# Mainsnode_v2_openmote.net
KiCad netlist of a schematic drawn in EAGLE
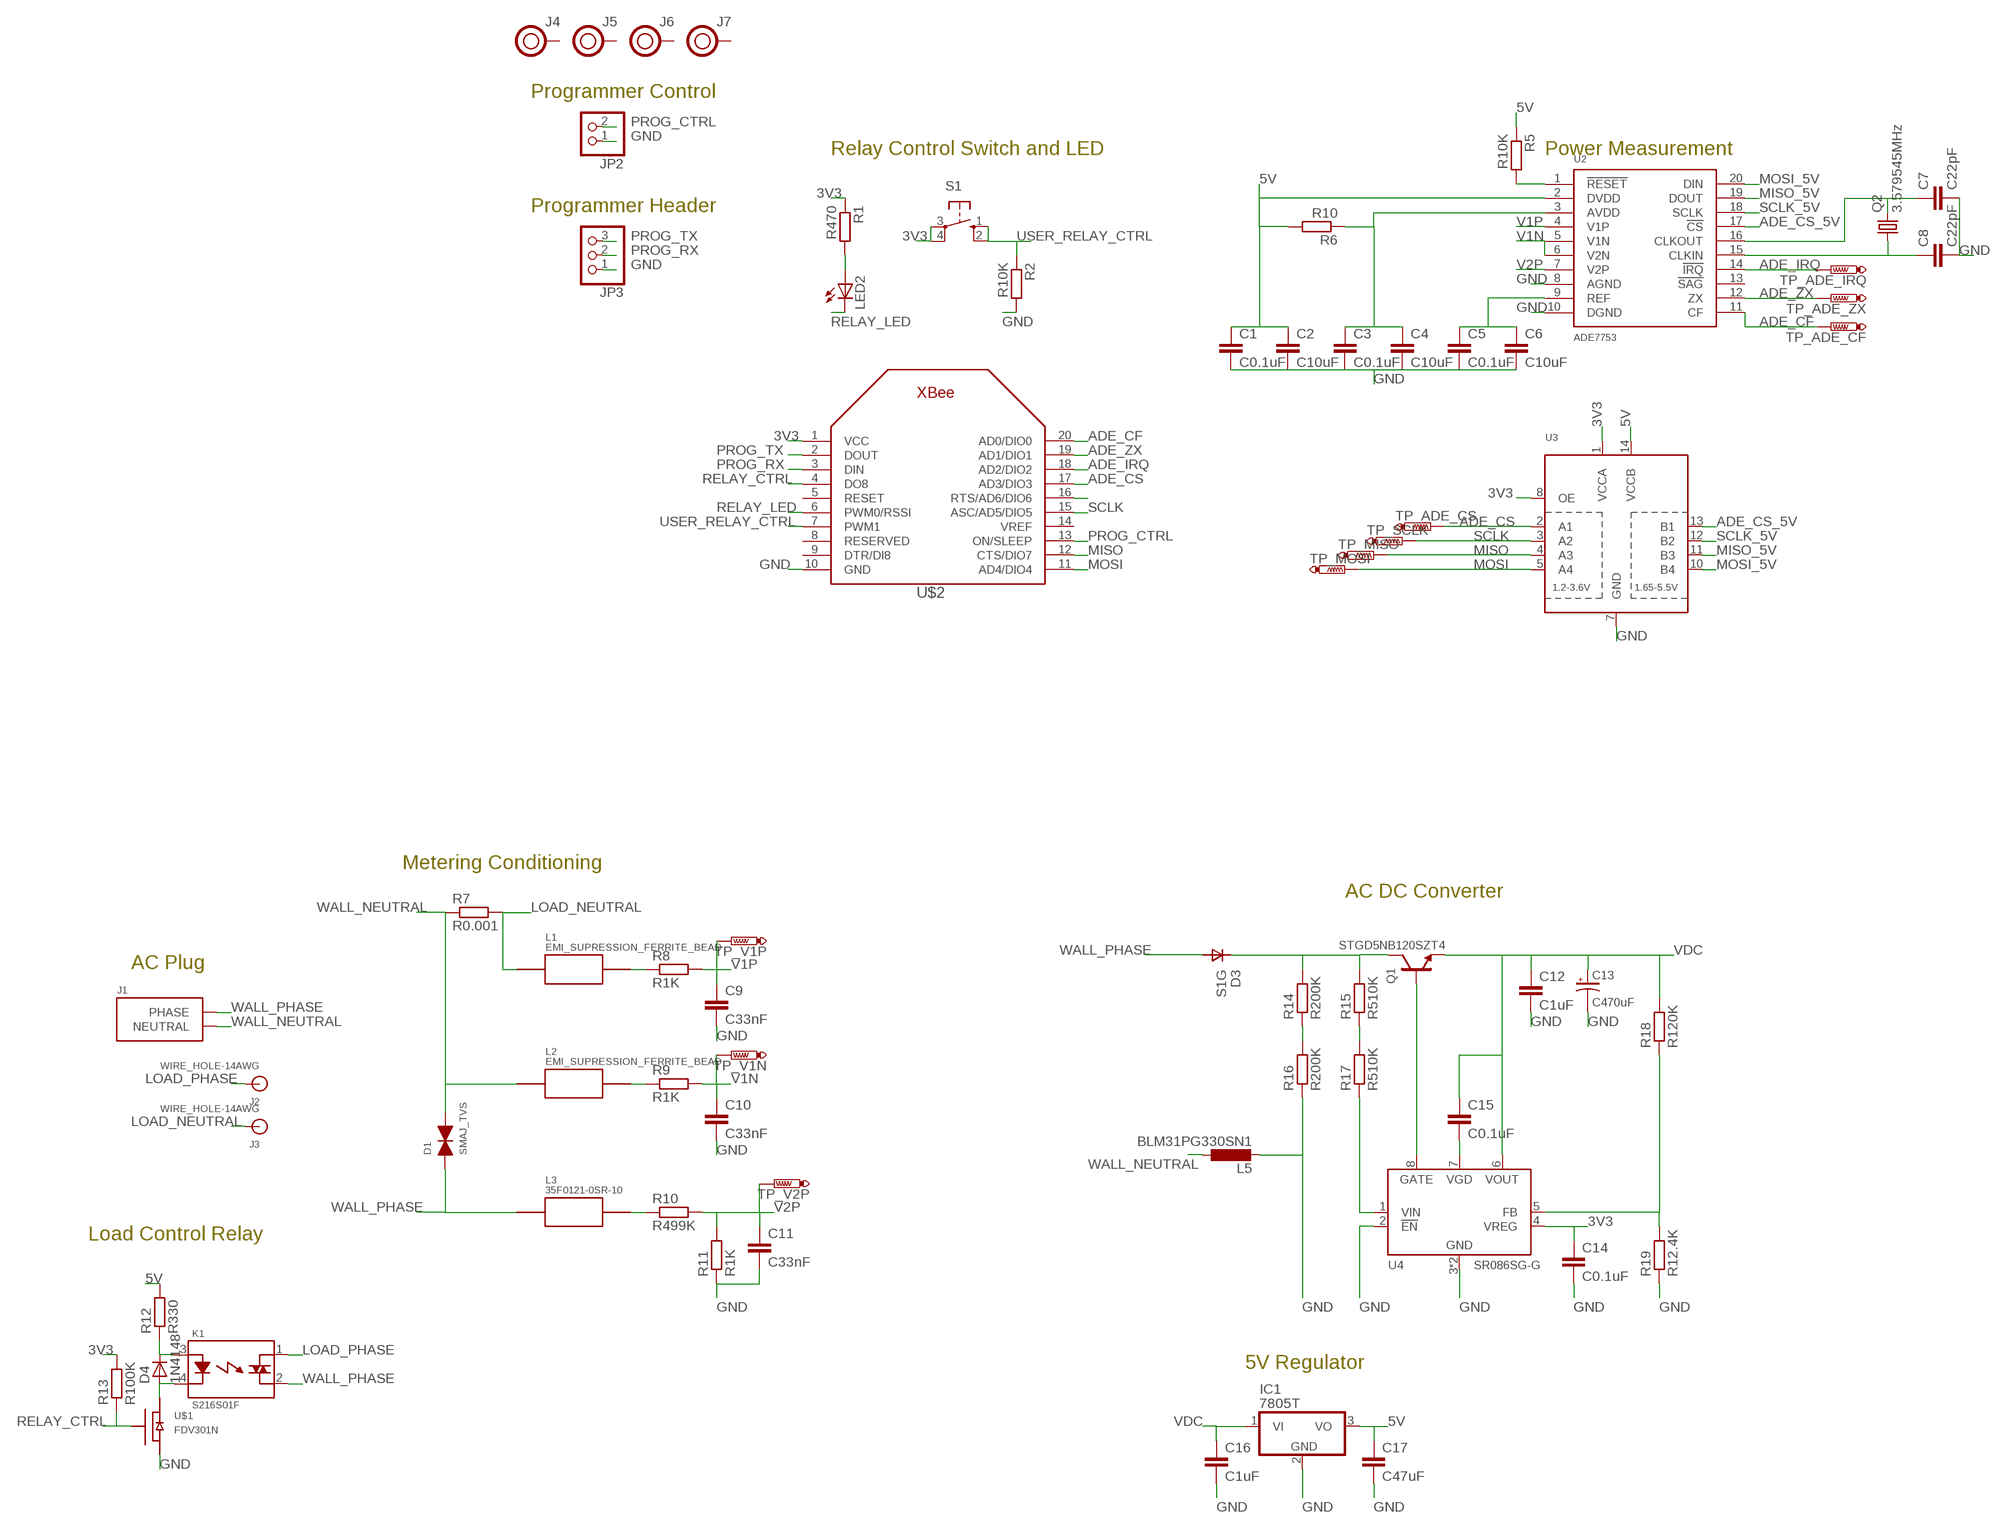
[diagram p0: schematic, sheet 1]

(export (version "E")
  (design (tool "Eeschema 10.0.6"))
  (components
    (comp (ref "C1")
      (value "C0.1uF")
      (footprint "eagle-import:C0805")
      (libsource (lib "eagle-import") (part "C-EUC0805"))
    )
    (comp (ref "C2")
      (value "C10uF")
      (footprint "eagle-import:C0805")
      (libsource (lib "eagle-import") (part "C-EUC0805"))
    )
    (comp (ref "C3")
      (value "C0.1uF")
      (footprint "eagle-import:C0805")
      (libsource (lib "eagle-import") (part "C-EUC0805"))
    )
    (comp (ref "C4")
      (value "C10uF")
      (footprint "eagle-import:C0805")
      (libsource (lib "eagle-import") (part "C-EUC0805"))
    )
    (comp (ref "C5")
      (value "C0.1uF")
      (footprint "eagle-import:C0805")
      (libsource (lib "eagle-import") (part "C-EUC0805"))
    )
    (comp (ref "C6")
      (value "C10uF")
      (footprint "eagle-import:C0805")
      (libsource (lib "eagle-import") (part "C-EUC0805"))
    )
    (comp (ref "C7")
      (value "C22pF")
      (footprint "eagle-import:C0805")
      (libsource (lib "eagle-import") (part "C-EUC0805"))
    )
    (comp (ref "C8")
      (value "C22pF")
      (footprint "eagle-import:C0805")
      (libsource (lib "eagle-import") (part "C-EUC0805"))
    )
    (comp (ref "C9")
      (value "C33nF")
      (footprint "eagle-import:C0805")
      (libsource (lib "eagle-import") (part "C-EUC0805"))
    )
    (comp (ref "C10")
      (value "C33nF")
      (footprint "eagle-import:C0805")
      (libsource (lib "eagle-import") (part "C-EUC0805"))
    )
    (comp (ref "C11")
      (value "C33nF")
      (footprint "eagle-import:C0805")
      (libsource (lib "eagle-import") (part "C-EUC0805"))
    )
    (comp (ref "C12")
      (value "C1uF")
      (footprint "eagle-import:C0805")
      (libsource (lib "eagle-import") (part "C-EUC0805"))
    )
    (comp (ref "C13")
      (value "C470uF")
      (footprint "eagle-import:CAP_SM_10MM")
      (libsource (lib "eagle-import") (part "CAP_EEE-FP1E471AP"))
    )
    (comp (ref "C14")
      (value "C0.1uF")
      (footprint "eagle-import:C0805")
      (libsource (lib "eagle-import") (part "C-EUC0805"))
    )
    (comp (ref "C15")
      (value "C0.1uF")
      (footprint "eagle-import:C0805")
      (libsource (lib "eagle-import") (part "C-EUC0805"))
    )
    (comp (ref "C16")
      (value "C1uF")
      (footprint "eagle-import:C0805")
      (libsource (lib "eagle-import") (part "C-EUC0805"))
    )
    (comp (ref "C17")
      (value "C47uF")
      (footprint "eagle-import:C0805")
      (libsource (lib "eagle-import") (part "C-EUC0805"))
    )
    (comp (ref "D1")
      (value "SMAJ_TVS")
      (footprint "eagle-import:DO214_TVS")
      (libsource (lib "eagle-import") (part "SMAJ_TVS"))
    )
    (comp (ref "D3")
      (value "S1G")
      (footprint "eagle-import:DO-214AC")
      (libsource (lib "eagle-import") (part "S1G"))
    )
    (comp (ref "D4")
      (value "1N4148")
      (footprint "eagle-import:SOD80")
      (libsource (lib "eagle-import") (part "D-SOD-80"))
    )
    (comp (ref "IC1")
      (value "7805T")
      (footprint "eagle-import:TO220H")
      (libsource (lib "eagle-import") (part "78T05"))
    )
    (comp (ref "J1")
      (value "AC-PLUG-2")
      (footprint "eagle-import:AC_MALE_PINS_2")
      (libsource (lib "eagle-import") (part "AC-PLUG-2"))
    )
    (comp (ref "J2")
      (value "WIRE_HOLE-14AWG")
      (footprint "eagle-import:WIRE_HOLE-14AWG")
      (libsource (lib "eagle-import") (part "WIRE_HOLE-14AWG"))
    )
    (comp (ref "J3")
      (value "WIRE_HOLE-14AWG")
      (footprint "eagle-import:WIRE_HOLE-14AWG")
      (libsource (lib "eagle-import") (part "WIRE_HOLE-14AWG"))
    )
    (comp (ref "J4")
      (value "HOLE")
      (footprint "eagle-import:HOLE-0.125")
      (libsource (lib "eagle-import") (part "HOLE"))
    )
    (comp (ref "J5")
      (value "HOLE")
      (footprint "eagle-import:HOLE-0.125")
      (libsource (lib "eagle-import") (part "HOLE"))
    )
    (comp (ref "J6")
      (value "HOLE")
      (footprint "eagle-import:HOLE-0.125")
      (libsource (lib "eagle-import") (part "HOLE"))
    )
    (comp (ref "J7")
      (value "HOLE")
      (footprint "eagle-import:HOLE-0.125")
      (libsource (lib "eagle-import") (part "HOLE"))
    )
    (comp (ref "JP2")
      (value "PINHD-1X2")
      (footprint "eagle-import:1X02")
      (libsource (lib "eagle-import") (part "PINHD-1X2"))
    )
    (comp (ref "JP3")
      (value "PINHD-1X3")
      (footprint "eagle-import:1X03")
      (libsource (lib "eagle-import") (part "PINHD-1X3"))
    )
    (comp (ref "K1")
      (value "S216S01F")
      (footprint "eagle-import:RELAY_SX16S0X")
      (libsource (lib "eagle-import") (part "S216S01F"))
    )
    (comp (ref "L1")
      (value "EMI_SUPRESSION_FERRITE_BEAD")
      (footprint "eagle-import:L1806")
      (libsource (lib "eagle-import") (part "EMI_SUPRESSION_FERRITE_BEAD"))
    )
    (comp (ref "L2")
      (value "EMI_SUPRESSION_FERRITE_BEAD")
      (footprint "eagle-import:L1806")
      (fields (field (name "DIGIKEY") "240-2418-1-ND"))
      (libsource (lib "eagle-import") (part "EMI_SUPRESSION_FERRITE_BEAD"))
    )
    (comp (ref "L3")
      (value "35F0121-0SR-10")
      (footprint "eagle-import:35F0102")
      (libsource (lib "eagle-import") (part "35F0121-0SR-10"))
    )
    (comp (ref "L5")
      (value "BLM31PG330SN1")
      (footprint "eagle-import:L3216C")
      (libsource (lib "eagle-import") (part "L-EUL3216C"))
    )
    (comp (ref "LED2")
      (value "LED3MM")
      (footprint "eagle-import:LED3MM")
      (libsource (lib "eagle-import") (part "LED3MM"))
    )
    (comp (ref "Q1")
      (value "STGD5NB120SZT4")
      (footprint "eagle-import:DPAK")
      (libsource (lib "eagle-import") (part "STGD5NB120SZT4"))
    )
    (comp (ref "Q2")
      (value "3.579545MHz")
      (footprint "eagle-import:HC49_S")
      (libsource (lib "eagle-import") (part "CRYSTALHC49S"))
    )
    (comp (ref "R1")
      (value "R470")
      (footprint "eagle-import:R0805")
      (libsource (lib "eagle-import") (part "R-EU_R0805"))
    )
    (comp (ref "R2")
      (value "R10K")
      (footprint "eagle-import:R0805")
      (libsource (lib "eagle-import") (part "R-EU_R0805"))
    )
    (comp (ref "R5")
      (value "R10K")
      (footprint "eagle-import:R0805")
      (libsource (lib "eagle-import") (part "R-EU_R0805"))
    )
    (comp (ref "R6")
      (value "R10")
      (footprint "eagle-import:R0805")
      (libsource (lib "eagle-import") (part "R-EU_R0805"))
    )
    (comp (ref "R7")
      (value "R0.001")
      (footprint "eagle-import:R2512")
      (libsource (lib "eagle-import") (part "R-EU_R2512"))
    )
    (comp (ref "R8")
      (value "R1K")
      (footprint "eagle-import:R0805")
      (libsource (lib "eagle-import") (part "R-EU_R0805"))
    )
    (comp (ref "R9")
      (value "R1K")
      (footprint "eagle-import:R0805")
      (libsource (lib "eagle-import") (part "R-EU_R0805"))
    )
    (comp (ref "R10")
      (value "R499K")
      (footprint "eagle-import:R0805")
      (libsource (lib "eagle-import") (part "R-EU_R0805"))
    )
    (comp (ref "R11")
      (value "R1K")
      (footprint "eagle-import:R0805")
      (libsource (lib "eagle-import") (part "R-EU_R0805"))
    )
    (comp (ref "R12")
      (value "R330")
      (footprint "eagle-import:R0805")
      (libsource (lib "eagle-import") (part "R-EU_R0805"))
    )
    (comp (ref "R13")
      (value "R100K")
      (footprint "eagle-import:R0805")
      (libsource (lib "eagle-import") (part "R-EU_R0805"))
    )
    (comp (ref "R14")
      (value "R200K")
      (footprint "eagle-import:R0805")
      (libsource (lib "eagle-import") (part "R-EU_R0805"))
    )
    (comp (ref "R15")
      (value "R510K")
      (footprint "eagle-import:R0805")
      (libsource (lib "eagle-import") (part "R-EU_R0805"))
    )
    (comp (ref "R16")
      (value "R200K")
      (footprint "eagle-import:R0805")
      (libsource (lib "eagle-import") (part "R-EU_R0805"))
    )
    (comp (ref "R17")
      (value "R510K")
      (footprint "eagle-import:R0805")
      (libsource (lib "eagle-import") (part "R-EU_R0805"))
    )
    (comp (ref "R18")
      (value "R120K")
      (footprint "eagle-import:R0805")
      (libsource (lib "eagle-import") (part "R-EU_R0805"))
    )
    (comp (ref "R19")
      (value "R12.4K")
      (footprint "eagle-import:R0805")
      (libsource (lib "eagle-import") (part "R-EU_R0805"))
    )
    (comp (ref "S1")
      (value "10-XX")
      (footprint "eagle-import:B3F-10XX")
      (fields (field (name "MPN") "B3F-1000"))
      (libsource (lib "eagle-import") (part "10-XX"))
    )
    (comp (ref "TP_ADE_CF")
      (value "PTR1PAD1-13")
      (footprint "eagle-import:P1-13")
      (libsource (lib "eagle-import") (part "PTR1PAD1-13"))
    )
    (comp (ref "TP_ADE_CS")
      (value "PTR1PAD1-13")
      (footprint "eagle-import:P1-13")
      (libsource (lib "eagle-import") (part "PTR1PAD1-13"))
    )
    (comp (ref "TP_ADE_IRQ")
      (value "PTR1PAD1-13")
      (footprint "eagle-import:P1-13")
      (libsource (lib "eagle-import") (part "PTR1PAD1-13"))
    )
    (comp (ref "TP_ADE_ZX")
      (value "PTR1PAD1-13")
      (footprint "eagle-import:P1-13")
      (libsource (lib "eagle-import") (part "PTR1PAD1-13"))
    )
    (comp (ref "TP_MISO")
      (value "PTR1PAD1-13")
      (footprint "eagle-import:P1-13")
      (libsource (lib "eagle-import") (part "PTR1PAD1-13"))
    )
    (comp (ref "TP_MOSI")
      (value "PTR1PAD1-13")
      (footprint "eagle-import:P1-13")
      (libsource (lib "eagle-import") (part "PTR1PAD1-13"))
    )
    (comp (ref "TP_SCLK")
      (value "PTR1PAD1-13")
      (footprint "eagle-import:P1-13")
      (libsource (lib "eagle-import") (part "PTR1PAD1-13"))
    )
    (comp (ref "TP_V1N")
      (value "PTR1PAD1-13")
      (footprint "eagle-import:P1-13")
      (libsource (lib "eagle-import") (part "PTR1PAD1-13"))
    )
    (comp (ref "TP_V1P")
      (value "PTR1PAD1-13")
      (footprint "eagle-import:P1-13")
      (libsource (lib "eagle-import") (part "PTR1PAD1-13"))
    )
    (comp (ref "TP_V2P")
      (value "PTR1PAD1-13")
      (footprint "eagle-import:P1-13")
      (libsource (lib "eagle-import") (part "PTR1PAD1-13"))
    )
    (comp (ref "U$1")
      (value "FDV301N")
      (footprint "eagle-import:SOT-23")
      (libsource (lib "eagle-import") (part "FDV301N"))
    )
    (comp (ref "U$2")
      (value "XBEE")
      (footprint "eagle-import:XBEE")
      (libsource (lib "eagle-import") (part "XBEE"))
    )
    (comp (ref "U2")
      (value "ADE7753")
      (footprint "eagle-import:SSOP-20")
      (libsource (lib "eagle-import") (part "ADE7753"))
    )
    (comp (ref "U3")
      (value "TXB0104PWR")
      (footprint "eagle-import:TSSOP14")
      (libsource (lib "eagle-import") (part "TXB0104PWR"))
    )
    (comp (ref "U4")
      (value "SR086SG-G")
      (footprint "eagle-import:SR086")
      (libsource (lib "eagle-import") (part "SR086SG-G"))
    )
  )
  (nets
    (net (code "1") (name "/3V3") (class "Default")
      (node (ref "C14") (pin "1") (pinfunction "1_1") (pintype "passive"))
      (node (ref "R1") (pin "1") (pinfunction "1_1") (pintype "passive"))
      (node (ref "R13") (pin "2") (pinfunction "2_2") (pintype "passive"))
      (node (ref "S1") (pin "3") (pinfunction "P_3") (pintype "passive"))
      (node (ref "S1") (pin "4") (pinfunction "P1_4") (pintype "passive"))
      (node (ref "U$2") (pin "1") (pinfunction "VCC_1") (pintype "power_in"))
      (node (ref "U3") (pin "1") (pinfunction "VCCA_1") (pintype "bidirectional"))
      (node (ref "U3") (pin "8") (pinfunction "OE_8") (pintype "bidirectional"))
      (node (ref "U4") (pin "4") (pinfunction "VREG_4") (pintype "bidirectional"))
    )
    (net (code "2") (name "/5V") (class "Default")
      (node (ref "C1") (pin "1") (pinfunction "1_1") (pintype "passive"))
      (node (ref "C17") (pin "1") (pinfunction "1_1") (pintype "passive"))
      (node (ref "C2") (pin "1") (pinfunction "1_1") (pintype "passive"))
      (node (ref "IC1") (pin "3") (pinfunction "VO_3") (pintype "passive"))
      (node (ref "R12") (pin "2") (pinfunction "2_2") (pintype "passive"))
      (node (ref "R5") (pin "1") (pinfunction "1_1") (pintype "passive"))
      (node (ref "R6") (pin "2") (pinfunction "2_2") (pintype "passive"))
      (node (ref "U2") (pin "2") (pinfunction "DVDD_2") (pintype "bidirectional"))
      (node (ref "U3") (pin "14") (pinfunction "VCCB_14") (pintype "bidirectional"))
    )
    (net (code "3") (name "/ADE_CF") (class "Default")
      (node (ref "TP_ADE_CF") (pin "TP") (pinfunction "TP_TP") (pintype "input"))
      (node (ref "U$2") (pin "20") (pinfunction "AD0/DIO0_20") (pintype "bidirectional"))
      (node (ref "U2") (pin "11") (pinfunction "CF_11") (pintype "bidirectional"))
    )
    (net (code "4") (name "/ADE_CS") (class "Default")
      (node (ref "TP_ADE_CS") (pin "TP") (pinfunction "TP_TP") (pintype "input"))
      (node (ref "U$2") (pin "17") (pinfunction "AD3/DIO3_17") (pintype "bidirectional"))
      (node (ref "U3") (pin "2") (pinfunction "A1_2") (pintype "bidirectional"))
    )
    (net (code "5") (name "/ADE_CS_5V") (class "Default")
      (node (ref "U2") (pin "17") (pinfunction "~{CS}_17") (pintype "bidirectional"))
      (node (ref "U3") (pin "13") (pinfunction "B1_13") (pintype "bidirectional"))
    )
    (net (code "6") (name "/ADE_IRQ") (class "Default")
      (node (ref "TP_ADE_IRQ") (pin "TP") (pinfunction "TP_TP") (pintype "input"))
      (node (ref "U$2") (pin "18") (pinfunction "AD2/DIO2_18") (pintype "bidirectional"))
      (node (ref "U2") (pin "14") (pinfunction "~{IRQ}_14") (pintype "bidirectional"))
    )
    (net (code "7") (name "/ADE_ZX") (class "Default")
      (node (ref "TP_ADE_ZX") (pin "TP") (pinfunction "TP_TP") (pintype "input"))
      (node (ref "U$2") (pin "19") (pinfunction "AD1/DIO1_19") (pintype "bidirectional"))
      (node (ref "U2") (pin "12") (pinfunction "ZX_12") (pintype "bidirectional"))
    )
    (net (code "8") (name "/GND") (class "Default")
      (node (ref "C1") (pin "2") (pinfunction "2_2") (pintype "passive"))
      (node (ref "C10") (pin "2") (pinfunction "2_2") (pintype "passive"))
      (node (ref "C11") (pin "2") (pinfunction "2_2") (pintype "passive"))
      (node (ref "C12") (pin "2") (pinfunction "2_2") (pintype "passive"))
      (node (ref "C13") (pin "-") (pinfunction "-_-") (pintype "bidirectional"))
      (node (ref "C14") (pin "2") (pinfunction "2_2") (pintype "passive"))
      (node (ref "C16") (pin "2") (pinfunction "2_2") (pintype "passive"))
      (node (ref "C17") (pin "2") (pinfunction "2_2") (pintype "passive"))
      (node (ref "C2") (pin "2") (pinfunction "2_2") (pintype "passive"))
      (node (ref "C3") (pin "2") (pinfunction "2_2") (pintype "passive"))
      (node (ref "C4") (pin "2") (pinfunction "2_2") (pintype "passive"))
      (node (ref "C5") (pin "2") (pinfunction "2_2") (pintype "passive"))
      (node (ref "C6") (pin "2") (pinfunction "2_2") (pintype "passive"))
      (node (ref "C7") (pin "2") (pinfunction "2_2") (pintype "passive"))
      (node (ref "C8") (pin "2") (pinfunction "2_2") (pintype "passive"))
      (node (ref "C9") (pin "2") (pinfunction "2_2") (pintype "passive"))
      (node (ref "IC1") (pin "2") (pinfunction "GND_2") (pintype "passive"))
      (node (ref "JP2") (pin "1") (pinfunction "1_1") (pintype "passive"))
      (node (ref "JP3") (pin "1") (pinfunction "1_1") (pintype "passive"))
      (node (ref "L5") (pin "2") (pinfunction "2_2") (pintype "passive"))
      (node (ref "R11") (pin "1") (pinfunction "1_1") (pintype "passive"))
      (node (ref "R16") (pin "1") (pinfunction "1_1") (pintype "passive"))
      (node (ref "R19") (pin "1") (pinfunction "1_1") (pintype "passive"))
      (node (ref "R2") (pin "2") (pinfunction "2_2") (pintype "passive"))
      (node (ref "U$1") (pin "2") (pinfunction "S_2") (pintype "bidirectional"))
      (node (ref "U$2") (pin "10") (pinfunction "GND_10") (pintype "power_in"))
      (node (ref "U2") (pin "10") (pinfunction "DGND_10") (pintype "bidirectional"))
      (node (ref "U2") (pin "8") (pinfunction "AGND_8") (pintype "bidirectional"))
      (node (ref "U3") (pin "7") (pinfunction "GND_7") (pintype "bidirectional"))
      (node (ref "U4") (pin "2") (pinfunction "~{EN}_2") (pintype "bidirectional"))
      (node (ref "U4") (pin "3") (pinfunction "GND_3") (pintype "bidirectional"))
      (node (ref "U4") (pin "PAD") (pinfunction "GND_PAD") (pintype "bidirectional"))
    )
    (net (code "9") (name "/LOAD_NEUTRAL") (class "Default")
      (node (ref "J3") (pin "P$1") (pinfunction "P$1_P$1") (pintype "bidirectional"))
      (node (ref "L1") (pin "P$1") (pinfunction "P$1_P$1") (pintype "bidirectional"))
      (node (ref "R7") (pin "2") (pinfunction "2_2") (pintype "passive"))
    )
    (net (code "10") (name "/LOAD_PHASE") (class "Default")
      (node (ref "J2") (pin "P$1") (pinfunction "P$1_P$1") (pintype "bidirectional"))
      (node (ref "K1") (pin "1") (pinfunction "1_1") (pintype "bidirectional"))
    )
    (net (code "11") (name "/MISO") (class "Default")
      (node (ref "TP_MISO") (pin "TP") (pinfunction "TP_TP") (pintype "input"))
      (node (ref "U$2") (pin "12") (pinfunction "CTS/DIO7_12") (pintype "bidirectional"))
      (node (ref "U3") (pin "4") (pinfunction "A3_4") (pintype "bidirectional"))
    )
    (net (code "12") (name "/MISO_5V") (class "Default")
      (node (ref "U2") (pin "19") (pinfunction "DOUT_19") (pintype "bidirectional"))
      (node (ref "U3") (pin "11") (pinfunction "B3_11") (pintype "bidirectional"))
    )
    (net (code "13") (name "/MOSI") (class "Default")
      (node (ref "TP_MOSI") (pin "TP") (pinfunction "TP_TP") (pintype "input"))
      (node (ref "U$2") (pin "11") (pinfunction "AD4/DIO4_11") (pintype "bidirectional"))
      (node (ref "U3") (pin "5") (pinfunction "A4_5") (pintype "bidirectional"))
    )
    (net (code "14") (name "/MOSI_5V") (class "Default")
      (node (ref "U2") (pin "20") (pinfunction "DIN_20") (pintype "bidirectional"))
      (node (ref "U3") (pin "10") (pinfunction "B4_10") (pintype "bidirectional"))
    )
    (net (code "15") (name "/PROG_CTRL") (class "Default")
      (node (ref "JP2") (pin "2") (pinfunction "2_2") (pintype "passive"))
      (node (ref "U$2") (pin "13") (pinfunction "ON/SLEEP_13") (pintype "output"))
    )
    (net (code "16") (name "/PROG_RX") (class "Default")
      (node (ref "JP3") (pin "2") (pinfunction "2_2") (pintype "passive"))
      (node (ref "U$2") (pin "3") (pinfunction "DIN_3") (pintype "input"))
    )
    (net (code "17") (name "/PROG_TX") (class "Default")
      (node (ref "JP3") (pin "3") (pinfunction "3_3") (pintype "passive"))
      (node (ref "U$2") (pin "2") (pinfunction "DOUT_2") (pintype "output"))
    )
    (net (code "18") (name "/RELAY_CTRL") (class "Default")
      (node (ref "R13") (pin "1") (pinfunction "1_1") (pintype "passive"))
      (node (ref "U$1") (pin "1") (pinfunction "G_1") (pintype "bidirectional"))
      (node (ref "U$2") (pin "4") (pinfunction "DO8_4") (pintype "output"))
    )
    (net (code "19") (name "/RELAY_LED") (class "Default")
      (node (ref "LED2") (pin "K") (pinfunction "C_K") (pintype "passive"))
      (node (ref "U$2") (pin "6") (pinfunction "PWM0/RSSI_6") (pintype "output"))
    )
    (net (code "20") (name "/SCLK") (class "Default")
      (node (ref "TP_SCLK") (pin "TP") (pinfunction "TP_TP") (pintype "input"))
      (node (ref "U$2") (pin "15") (pinfunction "ASC/AD5/DIO5_15") (pintype "bidirectional"))
      (node (ref "U3") (pin "3") (pinfunction "A2_3") (pintype "bidirectional"))
    )
    (net (code "21") (name "/SCLK_5V") (class "Default")
      (node (ref "U2") (pin "18") (pinfunction "SCLK_18") (pintype "bidirectional"))
      (node (ref "U3") (pin "12") (pinfunction "B2_12") (pintype "bidirectional"))
    )
    (net (code "22") (name "/USER_RELAY_CTRL") (class "Default")
      (node (ref "R2") (pin "1") (pinfunction "1_1") (pintype "passive"))
      (node (ref "S1") (pin "1") (pinfunction "S_1") (pintype "passive"))
      (node (ref "S1") (pin "2") (pinfunction "S1_2") (pintype "passive"))
      (node (ref "U$2") (pin "7") (pinfunction "PWM1_7") (pintype "output"))
    )
    (net (code "23") (name "/V1N") (class "Default")
      (node (ref "C10") (pin "1") (pinfunction "1_1") (pintype "passive"))
      (node (ref "R9") (pin "2") (pinfunction "2_2") (pintype "passive"))
      (node (ref "TP_V1N") (pin "TP") (pinfunction "TP_TP") (pintype "input"))
      (node (ref "U2") (pin "5") (pinfunction "V1N_5") (pintype "bidirectional"))
      (node (ref "U2") (pin "6") (pinfunction "V2N_6") (pintype "bidirectional"))
    )
    (net (code "24") (name "/V1P") (class "Default")
      (node (ref "C9") (pin "1") (pinfunction "1_1") (pintype "passive"))
      (node (ref "R8") (pin "2") (pinfunction "2_2") (pintype "passive"))
      (node (ref "TP_V1P") (pin "TP") (pinfunction "TP_TP") (pintype "input"))
      (node (ref "U2") (pin "4") (pinfunction "V1P_4") (pintype "bidirectional"))
    )
    (net (code "25") (name "/V2P") (class "Default")
      (node (ref "C11") (pin "1") (pinfunction "1_1") (pintype "passive"))
      (node (ref "R10") (pin "2") (pinfunction "2_2") (pintype "passive"))
      (node (ref "R11") (pin "2") (pinfunction "2_2") (pintype "passive"))
      (node (ref "TP_V2P") (pin "TP") (pinfunction "TP_TP") (pintype "input"))
      (node (ref "U2") (pin "7") (pinfunction "V2P_7") (pintype "bidirectional"))
    )
    (net (code "26") (name "/VDC") (class "Default")
      (node (ref "C12") (pin "1") (pinfunction "1_1") (pintype "passive"))
      (node (ref "C13") (pin "+") (pinfunction "+_+") (pintype "bidirectional"))
      (node (ref "C15") (pin "1") (pinfunction "1_1") (pintype "passive"))
      (node (ref "C16") (pin "1") (pinfunction "1_1") (pintype "passive"))
      (node (ref "IC1") (pin "1") (pinfunction "VI_1") (pintype "input"))
      (node (ref "Q1") (pin "P$3") (pinfunction "E_P$3") (pintype "bidirectional"))
      (node (ref "R18") (pin "2") (pinfunction "2_2") (pintype "passive"))
      (node (ref "U4") (pin "6") (pinfunction "VOUT_6") (pintype "bidirectional"))
    )
    (net (code "27") (name "/WALL_NEUTRAL") (class "Default")
      (node (ref "D1") (pin "CATHODE") (pinfunction "P$2_CATHODE") (pintype "bidirectional"))
      (node (ref "J1") (pin "NEUTRAL1") (pinfunction "NEUTRAL_NEUTRAL1") (pintype "bidirectional"))
      (node (ref "J1") (pin "NEUTRAL2") (pinfunction "NEUTRAL_NEUTRAL2") (pintype "bidirectional"))
      (node (ref "L2") (pin "P$1") (pinfunction "P$1_P$1") (pintype "bidirectional"))
      (node (ref "L5") (pin "1") (pinfunction "1_1") (pintype "passive"))
      (node (ref "R7") (pin "1") (pinfunction "1_1") (pintype "passive"))
    )
    (net (code "28") (name "/WALL_PHASE") (class "Default")
      (node (ref "D1") (pin "ANODE") (pinfunction "P$1_ANODE") (pintype "bidirectional"))
      (node (ref "D3") (pin "ANNODE") (pinfunction "ANNODE_ANNODE") (pintype "bidirectional"))
      (node (ref "J1") (pin "PHASE1") (pinfunction "PHASE_PHASE1") (pintype "bidirectional"))
      (node (ref "J1") (pin "PHASE2") (pinfunction "PHASE_PHASE2") (pintype "bidirectional"))
      (node (ref "K1") (pin "2") (pinfunction "2_2") (pintype "bidirectional"))
      (node (ref "L3") (pin "1") (pinfunction "P$1_1") (pintype "bidirectional"))
    )
    (net (code "29") (name "Net-(D4-A)") (class "Default")
      (node (ref "D4") (pin "2") (pinfunction "A_2") (pintype "passive"))
      (node (ref "K1") (pin "4") (pinfunction "4_4") (pintype "bidirectional"))
      (node (ref "U$1") (pin "3") (pinfunction "D_3") (pintype "bidirectional"))
    )
    (net (code "30") (name "Net-(D4-C)") (class "Default")
      (node (ref "D4") (pin "1") (pinfunction "C_1") (pintype "passive"))
      (node (ref "K1") (pin "3") (pinfunction "3_3") (pintype "bidirectional"))
      (node (ref "R12") (pin "1") (pinfunction "1_1") (pintype "passive"))
    )
    (net (code "31") (name "Net-(L1-PadP$2)") (class "Default")
      (node (ref "L1") (pin "P$2") (pinfunction "P$2_P$2") (pintype "bidirectional"))
      (node (ref "R8") (pin "1") (pinfunction "1_1") (pintype "passive"))
    )
    (net (code "32") (name "Net-(L2-PadP$2)") (class "Default")
      (node (ref "L2") (pin "P$2") (pinfunction "P$2_P$2") (pintype "bidirectional"))
      (node (ref "R9") (pin "1") (pinfunction "1_1") (pintype "passive"))
    )
    (net (code "33") (name "Net-(L3-P$2)") (class "Default")
      (node (ref "L3") (pin "2") (pinfunction "P$2_2") (pintype "bidirectional"))
      (node (ref "R10") (pin "1") (pinfunction "1_1") (pintype "passive"))
    )
    (net (code "34") (name "Net-(LED2-PadA)") (class "Default")
      (node (ref "LED2") (pin "A") (pinfunction "A_A") (pintype "passive"))
      (node (ref "R1") (pin "2") (pinfunction "2_2") (pintype "passive"))
    )
    (net (code "35") (name "Net-(Q1-C)") (class "Default")
      (node (ref "D3") (pin "CATHODE") (pinfunction "CATHODE_CATHODE") (pintype "bidirectional"))
      (node (ref "Q1") (pin "P$2") (pinfunction "C_P$2") (pintype "bidirectional"))
      (node (ref "R14") (pin "2") (pinfunction "2_2") (pintype "passive"))
      (node (ref "R15") (pin "2") (pinfunction "2_2") (pintype "passive"))
    )
    (net (code "36") (name "Net-(Q1-G)") (class "Default")
      (node (ref "Q1") (pin "P$1") (pinfunction "G_P$1") (pintype "bidirectional"))
      (node (ref "U4") (pin "8") (pinfunction "GATE_8") (pintype "bidirectional"))
    )
    (net (code "37") (name "Net-(R14-Pad1)") (class "Default")
      (node (ref "R14") (pin "1") (pinfunction "1_1") (pintype "passive"))
      (node (ref "R16") (pin "2") (pinfunction "2_2") (pintype "passive"))
    )
    (net (code "38") (name "Net-(R15-Pad1)") (class "Default")
      (node (ref "R15") (pin "1") (pinfunction "1_1") (pintype "passive"))
      (node (ref "R17") (pin "2") (pinfunction "2_2") (pintype "passive"))
    )
    (net (code "39") (name "Net-(U2-AVDD)") (class "Default")
      (node (ref "C3") (pin "1") (pinfunction "1_1") (pintype "passive"))
      (node (ref "C4") (pin "1") (pinfunction "1_1") (pintype "passive"))
      (node (ref "R6") (pin "1") (pinfunction "1_1") (pintype "passive"))
      (node (ref "U2") (pin "3") (pinfunction "AVDD_3") (pintype "bidirectional"))
    )
    (net (code "40") (name "Net-(U2-CLKIN)") (class "Default")
      (node (ref "C8") (pin "1") (pinfunction "1_1") (pintype "passive"))
      (node (ref "Q2") (pin "1") (pinfunction "1_1") (pintype "passive"))
      (node (ref "U2") (pin "15") (pinfunction "CLKIN_15") (pintype "bidirectional"))
    )
    (net (code "41") (name "Net-(U2-CLKOUT)") (class "Default")
      (node (ref "C7") (pin "1") (pinfunction "1_1") (pintype "passive"))
      (node (ref "Q2") (pin "2") (pinfunction "2_2") (pintype "passive"))
      (node (ref "U2") (pin "16") (pinfunction "CLKOUT_16") (pintype "bidirectional"))
    )
    (net (code "42") (name "Net-(U2-REF)") (class "Default")
      (node (ref "C5") (pin "1") (pinfunction "1_1") (pintype "passive"))
      (node (ref "C6") (pin "1") (pinfunction "1_1") (pintype "passive"))
      (node (ref "U2") (pin "9") (pinfunction "REF_9") (pintype "bidirectional"))
    )
    (net (code "43") (name "Net-(U2-~{RESET})") (class "Default")
      (node (ref "R5") (pin "2") (pinfunction "2_2") (pintype "passive"))
      (node (ref "U2") (pin "1") (pinfunction "~{RESET}_1") (pintype "bidirectional"))
    )
    (net (code "44") (name "Net-(U4-FB)") (class "Default")
      (node (ref "R18") (pin "1") (pinfunction "1_1") (pintype "passive"))
      (node (ref "R19") (pin "2") (pinfunction "2_2") (pintype "passive"))
      (node (ref "U4") (pin "5") (pinfunction "FB_5") (pintype "bidirectional"))
    )
    (net (code "45") (name "Net-(U4-VGD)") (class "Default")
      (node (ref "C15") (pin "2") (pinfunction "2_2") (pintype "passive"))
      (node (ref "U4") (pin "7") (pinfunction "VGD_7") (pintype "bidirectional"))
    )
    (net (code "46") (name "Net-(U4-VIN)") (class "Default")
      (node (ref "R17") (pin "1") (pinfunction "1_1") (pintype "passive"))
      (node (ref "U4") (pin "1") (pinfunction "VIN_1") (pintype "bidirectional"))
    )
    (net (code "47") (name "unconnected-(J4-P$1-Pad1)") (class "Default")
      (node (ref "J4") (pin "1") (pinfunction "P$1_1") (pintype "bidirectional"))
    )
    (net (code "48") (name "unconnected-(J5-P$1-Pad1)") (class "Default")
      (node (ref "J5") (pin "1") (pinfunction "P$1_1") (pintype "bidirectional"))
    )
    (net (code "49") (name "unconnected-(J6-P$1-Pad1)") (class "Default")
      (node (ref "J6") (pin "1") (pinfunction "P$1_1") (pintype "bidirectional"))
    )
    (net (code "50") (name "unconnected-(J7-P$1-Pad1)") (class "Default")
      (node (ref "J7") (pin "1") (pinfunction "P$1_1") (pintype "bidirectional"))
    )
    (net (code "51") (name "unconnected-(U$2-DTR{slash}DI8-Pad9)") (class "Default")
      (node (ref "U$2") (pin "9") (pinfunction "DTR/DI8_9") (pintype "input"))
    )
    (net (code "52") (name "unconnected-(U$2-RESERVED-Pad8)") (class "Default")
      (node (ref "U$2") (pin "8") (pinfunction "RESERVED_8") (pintype "no_connect"))
    )
    (net (code "53") (name "unconnected-(U$2-RESET-Pad5)") (class "Default")
      (node (ref "U$2") (pin "5") (pinfunction "RESET_5") (pintype "input"))
    )
    (net (code "54") (name "unconnected-(U$2-RTS{slash}AD6{slash}DIO6-Pad16)") (class "Default")
      (node (ref "U$2") (pin "16") (pinfunction "RTS/AD6/DIO6_16") (pintype "bidirectional"))
    )
    (net (code "55") (name "unconnected-(U$2-VREF-Pad14)") (class "Default")
      (node (ref "U$2") (pin "14") (pinfunction "VREF_14") (pintype "input"))
    )
    (net (code "56") (name "unconnected-(U2-~{SAG}-Pad13)") (class "Default")
      (node (ref "U2") (pin "13") (pinfunction "~{SAG}_13") (pintype "bidirectional"))
    )
  )
)
